# 6-Wheel_Sensors.net
KiCad netlist of a schematic drawn in Altium Designer
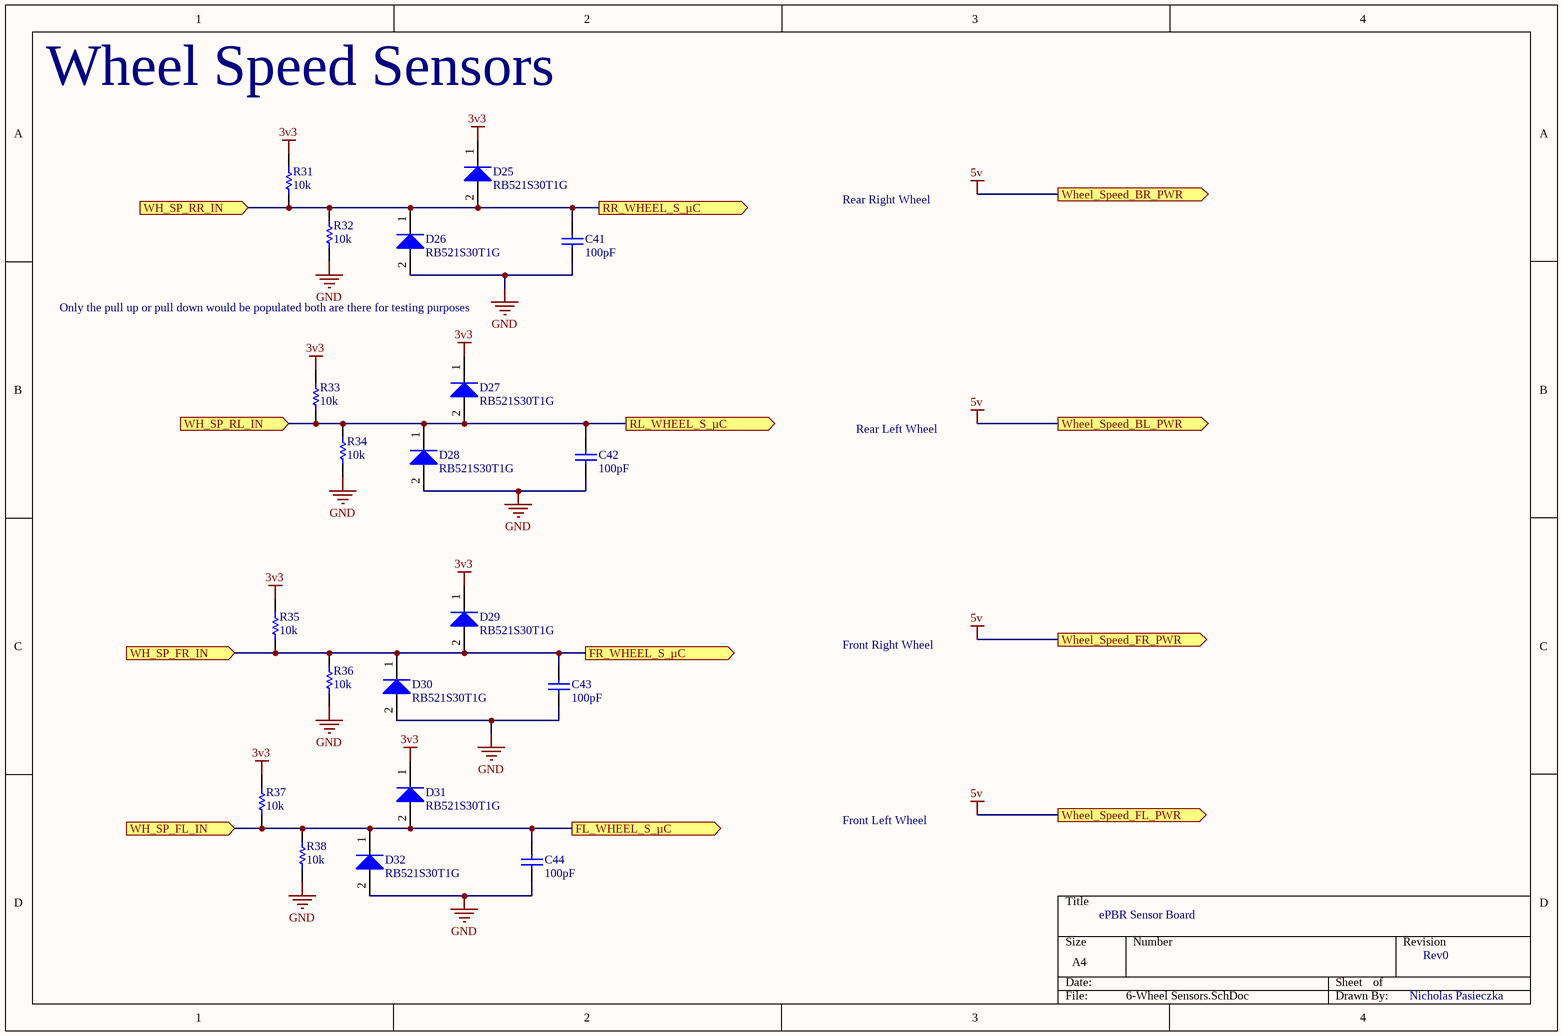
[diagram p0: 6-Wheel Sensors.SchDoc]

(export (version "E")
  (design (tool "Eeschema 10.0.6"))
  (components
    (comp (ref "C41")
      (value "100pF")
      (footprint "1608[0603]")
      (description "Capacitor")
      (fields (field (name "Comment") "Cap") (field (name "PUBLISHER") "Altium Limited"))
      (libsource (lib "Miscellaneous Devices") (part "Cap"))
    )
    (comp (ref "C42")
      (value "100pF")
      (footprint "1608[0603]")
      (description "Capacitor")
      (fields (field (name "Comment") "Cap") (field (name "PUBLISHER") "Altium Limited"))
      (libsource (lib "Miscellaneous Devices") (part "Cap"))
    )
    (comp (ref "C43")
      (value "100pF")
      (footprint "1608[0603]")
      (description "Capacitor")
      (fields (field (name "Comment") "Cap") (field (name "PUBLISHER") "Altium Limited"))
      (libsource (lib "Miscellaneous Devices") (part "Cap"))
    )
    (comp (ref "C44")
      (value "100pF")
      (footprint "1608[0603]")
      (description "Capacitor")
      (fields (field (name "Comment") "Cap") (field (name "PUBLISHER") "Altium Limited"))
      (libsource (lib "Miscellaneous Devices") (part "Cap"))
    )
    (comp (ref "D25")
      (value "RB521S30T1G")
      (footprint "ONSC-SOD-523-2-502-01_V")
      (description "Schottky Barrier Diode, 2-Pin SOD-523, Pb-Free, Tape and Reel")
      (fields (field (name "MANUFACTURER") "On Semiconductor"))
      (libsource (lib "Altium Content Vault") (part "ONSC-D-K1A2-2"))
    )
    (comp (ref "D26")
      (value "RB521S30T1G")
      (footprint "ONSC-SOD-523-2-502-01_V")
      (description "Schottky Barrier Diode, 2-Pin SOD-523, Pb-Free, Tape and Reel")
      (fields (field (name "MANUFACTURER") "On Semiconductor"))
      (libsource (lib "Altium Content Vault") (part "ONSC-D-K1A2-2"))
    )
    (comp (ref "D27")
      (value "RB521S30T1G")
      (footprint "ONSC-SOD-523-2-502-01_V")
      (description "Schottky Barrier Diode, 2-Pin SOD-523, Pb-Free, Tape and Reel")
      (fields (field (name "MANUFACTURER") "On Semiconductor"))
      (libsource (lib "Altium Content Vault") (part "ONSC-D-K1A2-2"))
    )
    (comp (ref "D28")
      (value "RB521S30T1G")
      (footprint "ONSC-SOD-523-2-502-01_V")
      (description "Schottky Barrier Diode, 2-Pin SOD-523, Pb-Free, Tape and Reel")
      (fields (field (name "MANUFACTURER") "On Semiconductor"))
      (libsource (lib "Altium Content Vault") (part "ONSC-D-K1A2-2"))
    )
    (comp (ref "D29")
      (value "RB521S30T1G")
      (footprint "ONSC-SOD-523-2-502-01_V")
      (description "Schottky Barrier Diode, 2-Pin SOD-523, Pb-Free, Tape and Reel")
      (fields (field (name "MANUFACTURER") "On Semiconductor"))
      (libsource (lib "Altium Content Vault") (part "ONSC-D-K1A2-2"))
    )
    (comp (ref "D30")
      (value "RB521S30T1G")
      (footprint "ONSC-SOD-523-2-502-01_V")
      (description "Schottky Barrier Diode, 2-Pin SOD-523, Pb-Free, Tape and Reel")
      (fields (field (name "MANUFACTURER") "On Semiconductor"))
      (libsource (lib "Altium Content Vault") (part "ONSC-D-K1A2-2"))
    )
    (comp (ref "D31")
      (value "RB521S30T1G")
      (footprint "ONSC-SOD-523-2-502-01_V")
      (description "Schottky Barrier Diode, 2-Pin SOD-523, Pb-Free, Tape and Reel")
      (fields (field (name "MANUFACTURER") "On Semiconductor"))
      (libsource (lib "Altium Content Vault") (part "ONSC-D-K1A2-2"))
    )
    (comp (ref "D32")
      (value "RB521S30T1G")
      (footprint "ONSC-SOD-523-2-502-01_V")
      (description "Schottky Barrier Diode, 2-Pin SOD-523, Pb-Free, Tape and Reel")
      (fields (field (name "MANUFACTURER") "On Semiconductor"))
      (libsource (lib "Altium Content Vault") (part "ONSC-D-K1A2-2"))
    )
    (comp (ref "R31")
      (value "10k")
      (footprint "1608[0603]")
      (description "Resistor")
      (fields
        (field (name "MANUFACTURER") "Yageo")
        (field (name "MANUFACTURER PART NUMBER") "RC0603JR-0710KL")
      )
      (libsource (lib "Miscellaneous Devices") (part "Res1"))
    )
    (comp (ref "R32")
      (value "10k")
      (footprint "1608[0603]")
      (description "Resistor")
      (fields
        (field (name "MANUFACTURER") "Yageo")
        (field (name "MANUFACTURER PART NUMBER") "RC0603JR-0710KL")
      )
      (libsource (lib "Miscellaneous Devices") (part "Res1"))
    )
    (comp (ref "R33")
      (value "10k")
      (footprint "1608[0603]")
      (description "Resistor")
      (fields
        (field (name "MANUFACTURER") "Yageo")
        (field (name "MANUFACTURER PART NUMBER") "RC0603JR-0710KL")
      )
      (libsource (lib "Miscellaneous Devices") (part "Res1"))
    )
    (comp (ref "R34")
      (value "10k")
      (footprint "1608[0603]")
      (description "Resistor")
      (fields
        (field (name "MANUFACTURER") "Yageo")
        (field (name "MANUFACTURER PART NUMBER") "RC0603JR-0710KL")
      )
      (libsource (lib "Miscellaneous Devices") (part "Res1"))
    )
    (comp (ref "R35")
      (value "10k")
      (footprint "1608[0603]")
      (description "Resistor")
      (fields
        (field (name "MANUFACTURER") "Yageo")
        (field (name "MANUFACTURER PART NUMBER") "RC0603JR-0710KL")
      )
      (libsource (lib "Miscellaneous Devices") (part "Res1"))
    )
    (comp (ref "R36")
      (value "10k")
      (footprint "1608[0603]")
      (description "Resistor")
      (fields
        (field (name "MANUFACTURER") "Yageo")
        (field (name "MANUFACTURER PART NUMBER") "RC0603JR-0710KL")
      )
      (libsource (lib "Miscellaneous Devices") (part "Res1"))
    )
    (comp (ref "R37")
      (value "10k")
      (footprint "1608[0603]")
      (description "Resistor")
      (fields
        (field (name "MANUFACTURER") "Yageo")
        (field (name "MANUFACTURER PART NUMBER") "RC0603JR-0710KL")
      )
      (libsource (lib "Miscellaneous Devices") (part "Res1"))
    )
    (comp (ref "R38")
      (value "10k")
      (footprint "1608[0603]")
      (description "Resistor")
      (fields
        (field (name "MANUFACTURER") "Yageo")
        (field (name "MANUFACTURER PART NUMBER") "RC0603JR-0710KL")
      )
      (libsource (lib "Miscellaneous Devices") (part "Res1"))
    )
  )
  (nets
    (net (code "1") (name "/FL_WHEEL_S_µC") (class "Default")
      (node (ref "C44") (pin "2") (pinfunction "2_2") (pintype "passive"))
      (node (ref "D31") (pin "2") (pinfunction "A_2") (pintype "passive"))
      (node (ref "D32") (pin "1") (pinfunction "K_1") (pintype "passive"))
      (node (ref "R37") (pin "1") (pinfunction "1_1") (pintype "passive"))
      (node (ref "R38") (pin "2") (pinfunction "2_2") (pintype "passive"))
    )
    (net (code "2") (name "/FR_WHEEL_S_µC") (class "Default")
      (node (ref "C43") (pin "2") (pinfunction "2_2") (pintype "passive"))
      (node (ref "D29") (pin "2") (pinfunction "A_2") (pintype "passive"))
      (node (ref "D30") (pin "1") (pinfunction "K_1") (pintype "passive"))
      (node (ref "R35") (pin "1") (pinfunction "1_1") (pintype "passive"))
      (node (ref "R36") (pin "2") (pinfunction "2_2") (pintype "passive"))
    )
    (net (code "3") (name "/RL_WHEEL_S_µC") (class "Default")
      (node (ref "C42") (pin "2") (pinfunction "2_2") (pintype "passive"))
      (node (ref "D27") (pin "2") (pinfunction "A_2") (pintype "passive"))
      (node (ref "D28") (pin "1") (pinfunction "K_1") (pintype "passive"))
      (node (ref "R33") (pin "1") (pinfunction "1_1") (pintype "passive"))
      (node (ref "R34") (pin "2") (pinfunction "2_2") (pintype "passive"))
    )
    (net (code "4") (name "/RR_WHEEL_S_µC") (class "Default")
      (node (ref "C41") (pin "2") (pinfunction "2_2") (pintype "passive"))
      (node (ref "D25") (pin "2") (pinfunction "A_2") (pintype "passive"))
      (node (ref "D26") (pin "1") (pinfunction "K_1") (pintype "passive"))
      (node (ref "R31") (pin "1") (pinfunction "1_1") (pintype "passive"))
      (node (ref "R32") (pin "2") (pinfunction "2_2") (pintype "passive"))
    )
    (net (code "5") (name "3v3") (class "Default")
      (node (ref "D25") (pin "1") (pinfunction "K_1") (pintype "passive"))
      (node (ref "D27") (pin "1") (pinfunction "K_1") (pintype "passive"))
      (node (ref "D29") (pin "1") (pinfunction "K_1") (pintype "passive"))
      (node (ref "D31") (pin "1") (pinfunction "K_1") (pintype "passive"))
      (node (ref "R31") (pin "2") (pinfunction "2_2") (pintype "passive"))
      (node (ref "R33") (pin "2") (pinfunction "2_2") (pintype "passive"))
      (node (ref "R35") (pin "2") (pinfunction "2_2") (pintype "passive"))
      (node (ref "R37") (pin "2") (pinfunction "2_2") (pintype "passive"))
    )
    (net (code "7") (name "GND") (class "Default")
      (node (ref "C41") (pin "1") (pinfunction "1_1") (pintype "passive"))
      (node (ref "C42") (pin "1") (pinfunction "1_1") (pintype "passive"))
      (node (ref "C43") (pin "1") (pinfunction "1_1") (pintype "passive"))
      (node (ref "C44") (pin "1") (pinfunction "1_1") (pintype "passive"))
      (node (ref "D26") (pin "2") (pinfunction "A_2") (pintype "passive"))
      (node (ref "D28") (pin "2") (pinfunction "A_2") (pintype "passive"))
      (node (ref "D30") (pin "2") (pinfunction "A_2") (pintype "passive"))
      (node (ref "D32") (pin "2") (pinfunction "A_2") (pintype "passive"))
      (node (ref "R32") (pin "1") (pinfunction "1_1") (pintype "passive"))
      (node (ref "R34") (pin "1") (pinfunction "1_1") (pintype "passive"))
      (node (ref "R36") (pin "1") (pinfunction "1_1") (pintype "passive"))
      (node (ref "R38") (pin "1") (pinfunction "1_1") (pintype "passive"))
    )
  )
)
